# ADC.net
KiCad netlist of a schematic drawn in EAGLE
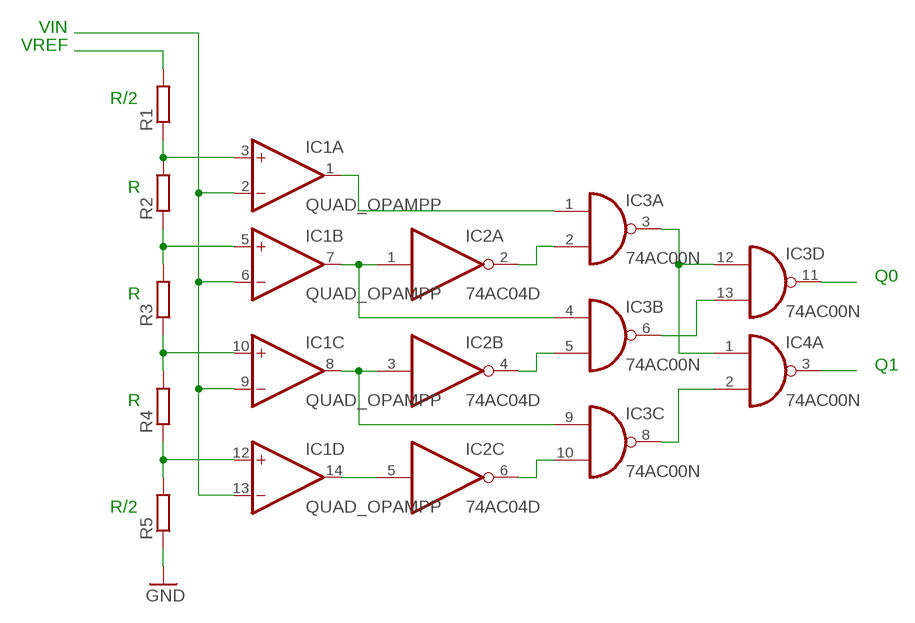
[diagram p0: schematic, sheet 1]

(export (version "E")
  (design (tool "Eeschema 10.0.6"))
  (components
    (comp (ref "IC1")
      (value "QUAD_OPAMPP")
      (footprint "eagle-import:DIL14")
      (libsource (lib "eagle-import") (part "QUAD_OPAMPP"))
    )
    (comp (ref "IC2")
      (value "74AC04D")
      (footprint "eagle-import:SO14")
      (libsource (lib "eagle-import") (part "7404DAC"))
    )
    (comp (ref "IC3")
      (value "74AC00N")
      (footprint "eagle-import:DIL14")
      (libsource (lib "eagle-import") (part "7400NAC"))
    )
    (comp (ref "IC4")
      (value "74AC00N")
      (footprint "eagle-import:DIL14")
      (libsource (lib "eagle-import") (part "7400NAC"))
    )
    (comp (ref "R1")
      (value "R-EU_0207/15")
      (footprint "eagle-import:0207_15")
      (libsource (lib "eagle-import") (part "R-EU_0207/15"))
    )
    (comp (ref "R2")
      (value "R-EU_0207/15")
      (footprint "eagle-import:0207_15")
      (libsource (lib "eagle-import") (part "R-EU_0207/15"))
    )
    (comp (ref "R3")
      (value "R-EU_0207/15")
      (footprint "eagle-import:0207_15")
      (libsource (lib "eagle-import") (part "R-EU_0207/15"))
    )
    (comp (ref "R4")
      (value "R-EU_0207/15")
      (footprint "eagle-import:0207_15")
      (libsource (lib "eagle-import") (part "R-EU_0207/15"))
    )
    (comp (ref "R5")
      (value "R-EU_0207/15")
      (footprint "eagle-import:0207_15")
      (libsource (lib "eagle-import") (part "R-EU_0207/15"))
    )
  )
  (nets
    (net (code "1") (name "GND") (class "Default")
      (node (ref "R5") (pin "1") (pinfunction "1_1") (pintype "passive"))
    )
    (net (code "2") (name "Net-(IC1A-+IN)") (class "Default")
      (node (ref "IC1") (pin "3") (pinfunction "+IN_3") (pintype "input"))
      (node (ref "R1") (pin "1") (pinfunction "1_1") (pintype "passive"))
      (node (ref "R2") (pin "2") (pinfunction "2_2") (pintype "passive"))
    )
    (net (code "3") (name "Net-(IC1A--IN)") (class "Default")
      (node (ref "IC1") (pin "13") (pinfunction "-IN_13") (pintype "input"))
      (node (ref "IC1") (pin "2") (pinfunction "-IN_2") (pintype "input"))
      (node (ref "IC1") (pin "6") (pinfunction "-IN_6") (pintype "input"))
      (node (ref "IC1") (pin "9") (pinfunction "-IN_9") (pintype "input"))
    )
    (net (code "4") (name "Net-(IC1A-OUT)") (class "Default")
      (node (ref "IC1") (pin "1") (pinfunction "OUT_1") (pintype "output"))
      (node (ref "IC3") (pin "1") (pinfunction "I0_1") (pintype "input"))
    )
    (net (code "5") (name "Net-(IC1B-+IN)") (class "Default")
      (node (ref "IC1") (pin "5") (pinfunction "+IN_5") (pintype "input"))
      (node (ref "R2") (pin "1") (pinfunction "1_1") (pintype "passive"))
      (node (ref "R3") (pin "2") (pinfunction "2_2") (pintype "passive"))
    )
    (net (code "6") (name "Net-(IC1B-OUT)") (class "Default")
      (node (ref "IC1") (pin "7") (pinfunction "OUT_7") (pintype "output"))
      (node (ref "IC2") (pin "1") (pinfunction "I_1") (pintype "input"))
      (node (ref "IC3") (pin "4") (pinfunction "I0_4") (pintype "input"))
    )
    (net (code "7") (name "Net-(IC1C-+IN)") (class "Default")
      (node (ref "IC1") (pin "10") (pinfunction "+IN_10") (pintype "input"))
      (node (ref "R3") (pin "1") (pinfunction "1_1") (pintype "passive"))
      (node (ref "R4") (pin "2") (pinfunction "2_2") (pintype "passive"))
    )
    (net (code "8") (name "Net-(IC1C-OUT)") (class "Default")
      (node (ref "IC1") (pin "8") (pinfunction "OUT_8") (pintype "output"))
      (node (ref "IC2") (pin "3") (pinfunction "I_3") (pintype "input"))
      (node (ref "IC3") (pin "9") (pinfunction "I0_9") (pintype "input"))
    )
    (net (code "9") (name "Net-(IC1D-+IN)") (class "Default")
      (node (ref "IC1") (pin "12") (pinfunction "+IN_12") (pintype "input"))
      (node (ref "R4") (pin "1") (pinfunction "1_1") (pintype "passive"))
      (node (ref "R5") (pin "2") (pinfunction "2_2") (pintype "passive"))
    )
    (net (code "10") (name "Net-(IC1D-OUT)") (class "Default")
      (node (ref "IC1") (pin "14") (pinfunction "OUT_14") (pintype "output"))
      (node (ref "IC2") (pin "5") (pinfunction "I_5") (pintype "input"))
    )
    (net (code "11") (name "Net-(IC2A-O)") (class "Default")
      (node (ref "IC2") (pin "2") (pinfunction "O_2") (pintype "output"))
      (node (ref "IC3") (pin "2") (pinfunction "I1_2") (pintype "input"))
    )
    (net (code "12") (name "Net-(IC2B-O)") (class "Default")
      (node (ref "IC2") (pin "4") (pinfunction "O_4") (pintype "output"))
      (node (ref "IC3") (pin "5") (pinfunction "I1_5") (pintype "input"))
    )
    (net (code "13") (name "Net-(IC2C-O)") (class "Default")
      (node (ref "IC2") (pin "6") (pinfunction "O_6") (pintype "output"))
      (node (ref "IC3") (pin "10") (pinfunction "I1_10") (pintype "input"))
    )
    (net (code "14") (name "Net-(IC3A-O)") (class "Default")
      (node (ref "IC3") (pin "12") (pinfunction "I0_12") (pintype "input"))
      (node (ref "IC3") (pin "3") (pinfunction "O_3") (pintype "output"))
      (node (ref "IC4") (pin "1") (pinfunction "I0_1") (pintype "input"))
    )
    (net (code "15") (name "Net-(IC3B-O)") (class "Default")
      (node (ref "IC3") (pin "13") (pinfunction "I1_13") (pintype "input"))
      (node (ref "IC3") (pin "6") (pinfunction "O_6") (pintype "output"))
    )
    (net (code "16") (name "Net-(IC3C-O)") (class "Default")
      (node (ref "IC3") (pin "8") (pinfunction "O_8") (pintype "output"))
      (node (ref "IC4") (pin "2") (pinfunction "I1_2") (pintype "input"))
    )
    (net (code "17") (name "unconnected-(IC3D-O-Pad11)") (class "Default")
      (node (ref "IC3") (pin "11") (pinfunction "O_11") (pintype "output"))
    )
    (net (code "18") (name "unconnected-(IC4A-O-Pad3)") (class "Default")
      (node (ref "IC4") (pin "3") (pinfunction "O_3") (pintype "output"))
    )
    (net (code "19") (name "unconnected-(R1-Pad2)") (class "Default")
      (node (ref "R1") (pin "2") (pinfunction "2_2") (pintype "passive"))
    )
  )
)
